# RS485_RS232_Sheet.net
KiCad netlist of a schematic drawn in Altium Designer
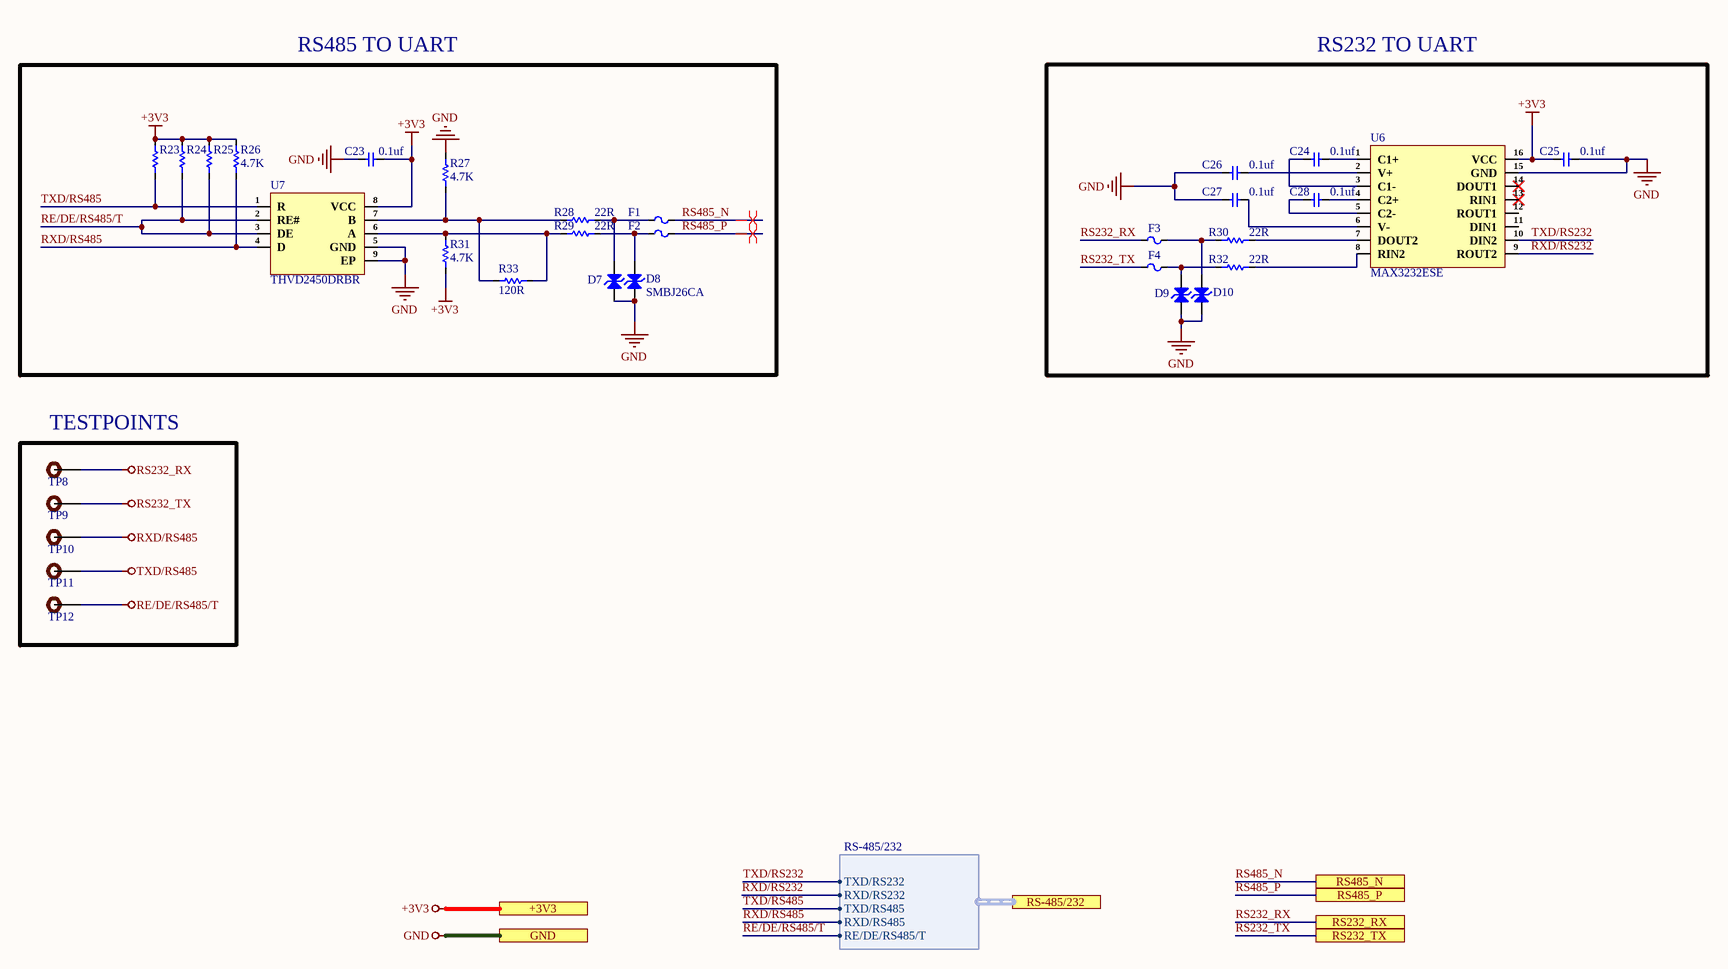
[diagram p0: RS485_RS232_Sheet.SchDoc]

(export (version "E")
  (design (tool "Eeschema 10.0.6"))
  (components
    (comp (ref "C23")
      (value "0.1uf")
      (footprint "Cap-0402")
      (description "CAP CER 0.1UF 100V X5R 0402")
      (fields
        (field (name "MANUFACTURER") "Murata")
        (field (name "MANUFACTURER PART NUMBER") "GRM155R62A104KE14D")
      )
      (libsource (lib "eSpark Libraries") (part "GRM155R62A104KE14D"))
    )
    (comp (ref "C24")
      (value "0.1uf")
      (footprint "Cap-0402")
      (description "CAP CER 0.1UF 100V X5R 0402")
      (fields
        (field (name "MANUFACTURER") "Murata")
        (field (name "MANUFACTURER PART NUMBER") "GRM155R62A104KE14D")
      )
      (libsource (lib "eSpark Libraries") (part "GRM155R62A104KE14D"))
    )
    (comp (ref "C25")
      (value "0.1uf")
      (footprint "Cap-0402")
      (description "CAP CER 0.1UF 100V X5R 0402")
      (fields
        (field (name "MANUFACTURER") "Murata")
        (field (name "MANUFACTURER PART NUMBER") "GRM155R62A104KE14D")
      )
      (libsource (lib "eSpark Libraries") (part "GRM155R62A104KE14D"))
    )
    (comp (ref "C26")
      (value "0.1uf")
      (footprint "Cap-0402")
      (description "CAP CER 0.1UF 100V X5R 0402")
      (fields
        (field (name "MANUFACTURER") "Murata")
        (field (name "MANUFACTURER PART NUMBER") "GRM155R62A104KE14D")
      )
      (libsource (lib "eSpark Libraries") (part "GRM155R62A104KE14D"))
    )
    (comp (ref "C27")
      (value "0.1uf")
      (footprint "Cap-0402")
      (description "CAP CER 0.1UF 100V X5R 0402")
      (fields
        (field (name "MANUFACTURER") "Murata")
        (field (name "MANUFACTURER PART NUMBER") "GRM155R62A104KE14D")
      )
      (libsource (lib "eSpark Libraries") (part "GRM155R62A104KE14D"))
    )
    (comp (ref "C28")
      (value "0.1uf")
      (footprint "Cap-0402")
      (description "CAP CER 0.1UF 100V X5R 0402")
      (fields
        (field (name "MANUFACTURER") "Murata")
        (field (name "MANUFACTURER PART NUMBER") "GRM155R62A104KE14D")
      )
      (libsource (lib "eSpark Libraries") (part "GRM155R62A104KE14D"))
    )
    (comp (ref "D7")
      (value "SMBJ26CA")
      (footprint "SMB Bi Directional")
      (description "SMB(DO-214AA) TVS ROHS")
      (fields (field (name "MANUFACTURER") "MSKSEMI") (field (name "LCSC PART NUMBER") "C5331111"))
      (libsource (lib "eSpark Libraries") (part "SMBJ26CA"))
    )
    (comp (ref "D8")
      (value "SMBJ26CA")
      (footprint "SMB Bi Directional")
      (description "SMB(DO-214AA) TVS ROHS")
      (fields (field (name "MANUFACTURER") "MSKSEMI") (field (name "LCSC PART NUMBER") "C5331111"))
      (libsource (lib "eSpark Libraries") (part "SMBJ26CA"))
    )
    (comp (ref "D9")
      (value "SMBJ26CA")
      (footprint "SMB Bi Directional")
      (description "SMB(DO-214AA) TVS ROHS")
      (fields (field (name "MANUFACTURER") "MSKSEMI") (field (name "LCSC PART NUMBER") "C5331111"))
      (libsource (lib "eSpark Libraries") (part "SMBJ26CA"))
    )
    (comp (ref "D10")
      (value "SMBJ26CA")
      (footprint "SMB Bi Directional")
      (description "SMB(DO-214AA) TVS ROHS")
      (fields (field (name "MANUFACTURER") "MSKSEMI") (field (name "LCSC PART NUMBER") "C5331111"))
      (libsource (lib "eSpark Libraries") (part "SMBJ26CA"))
    )
    (comp (ref "F1")
      (value "SMD0805P020TF")
      (footprint "Fuse-0805")
      (description "9V 200mA 100A 500mA 0805 Resettable Fuses ROHS")
      (fields (field (name "MANUFACTURER") "RUILON") (field (name "LCSC PART NUMBER") "C20976"))
      (libsource (lib "eSpark_centralized_Library(2022)") (part "SMD0805P020TF"))
    )
    (comp (ref "F2")
      (value "SMD0805P020TF")
      (footprint "Fuse-0805")
      (description "9V 200mA 100A 500mA 0805 Resettable Fuses ROHS")
      (fields (field (name "MANUFACTURER") "RUILON") (field (name "LCSC PART NUMBER") "C20976"))
      (libsource (lib "eSpark_centralized_Library(2022)") (part "SMD0805P020TF"))
    )
    (comp (ref "F3")
      (value "SMD0805P020TF")
      (footprint "Fuse-0805")
      (description "9V 200mA 100A 500mA 0805 Resettable Fuses ROHS")
      (fields (field (name "MANUFACTURER") "RUILON") (field (name "LCSC PART NUMBER") "C20976"))
      (libsource (lib "eSpark Libraries") (part "SMD0805P020TF"))
    )
    (comp (ref "F4")
      (value "SMD0805P020TF")
      (footprint "Fuse-0805")
      (description "9V 200mA 100A 500mA 0805 Resettable Fuses ROHS")
      (fields (field (name "MANUFACTURER") "RUILON") (field (name "LCSC PART NUMBER") "C20976"))
      (libsource (lib "eSpark Libraries") (part "SMD0805P020TF"))
    )
    (comp (ref "R23")
      (value "4.7K")
      (footprint "Res-0402")
      (description "RES 4.7K OHM 1% 1/16W 0402")
      (fields
        (field (name "MANUFACTURER") "Yageo")
        (field (name "MANUFACTURER PART NUMBER") "RC0402FR-074K7L")
      )
      (libsource (lib "eSpark Libraries") (part "RC0402FR-074K7L"))
    )
    (comp (ref "R24")
      (value "4.7K")
      (footprint "Res-0402")
      (description "RES 4.7K OHM 1% 1/16W 0402")
      (fields
        (field (name "MANUFACTURER") "Yageo")
        (field (name "MANUFACTURER PART NUMBER") "RC0402FR-074K7L")
      )
      (libsource (lib "eSpark Libraries") (part "RC0402FR-074K7L"))
    )
    (comp (ref "R25")
      (value "4.7K")
      (footprint "Res-0402")
      (description "RES 4.7K OHM 1% 1/16W 0402")
      (fields
        (field (name "MANUFACTURER") "Yageo")
        (field (name "MANUFACTURER PART NUMBER") "RC0402FR-074K7L")
      )
      (libsource (lib "eSpark Libraries") (part "RC0402FR-074K7L"))
    )
    (comp (ref "R26")
      (value "4.7K")
      (footprint "Res-0402")
      (description "RES 4.7K OHM 1% 1/16W 0402")
      (fields
        (field (name "MANUFACTURER") "Yageo")
        (field (name "MANUFACTURER PART NUMBER") "RC0402FR-074K7L")
      )
      (libsource (lib "eSpark Libraries") (part "RC0402FR-074K7L"))
    )
    (comp (ref "R27")
      (value "4.7K")
      (footprint "Res-0402")
      (description "RES 4.7K OHM 1% 1/16W 0402")
      (fields
        (field (name "MANUFACTURER") "Yageo")
        (field (name "MANUFACTURER PART NUMBER") "RC0402FR-074K7L")
      )
      (libsource (lib "eSpark Libraries") (part "RC0402FR-074K7L"))
    )
    (comp (ref "R28")
      (value "22R")
      (footprint "Res-0201")
      (description "RES 22 OHM 1% 1/20W 0201")
      (fields
        (field (name "MANUFACTURER") "Yageo")
        (field (name "MANUFACTURER PART NUMBER") "RC0201FR-0722RL")
      )
      (libsource (lib "eSpark Libraries") (part "RC0201FR-0722RL"))
    )
    (comp (ref "R29")
      (value "22R")
      (footprint "Res-0201")
      (description "RES 22 OHM 1% 1/20W 0201")
      (fields
        (field (name "MANUFACTURER") "Yageo")
        (field (name "MANUFACTURER PART NUMBER") "RC0201FR-0722RL")
      )
      (libsource (lib "eSpark Libraries") (part "RC0201FR-0722RL"))
    )
    (comp (ref "R30")
      (value "22R")
      (footprint "Res-0201")
      (description "RES 22 OHM 1% 1/20W 0201")
      (fields
        (field (name "MANUFACTURER") "Yageo")
        (field (name "MANUFACTURER PART NUMBER") "RC0201FR-0722RL")
      )
      (libsource (lib "eSpark Libraries") (part "RC0201FR-0722RL"))
    )
    (comp (ref "R31")
      (value "4.7K")
      (footprint "Res-0402")
      (description "RES 4.7K OHM 1% 1/16W 0402")
      (fields
        (field (name "MANUFACTURER") "Yageo")
        (field (name "MANUFACTURER PART NUMBER") "RC0402FR-074K7L")
      )
      (libsource (lib "eSpark Libraries") (part "RC0402FR-074K7L"))
    )
    (comp (ref "R32")
      (value "22R")
      (footprint "Res-0201")
      (description "RES 22 OHM 1% 1/20W 0201")
      (fields
        (field (name "MANUFACTURER") "Yageo")
        (field (name "MANUFACTURER PART NUMBER") "RC0201FR-0722RL")
      )
      (libsource (lib "eSpark Libraries") (part "RC0201FR-0722RL"))
    )
    (comp (ref "R33")
      (value "120R")
      (footprint "Res-0603")
      (description "RES 120 OHM 5% 1/10W 0603")
      (fields
        (field (name "MANUFACTURER") "Yageo")
        (field (name "MANUFACTURER PART NUMBER") "RC0603JR-07120RL")
      )
      (libsource (lib "eSpark Libraries") (part "RC0603JR-07120RL"))
    )
    (comp (ref "TP8")
      (value "TEST POINT")
      (footprint "Test-point")
      (description "Test Point ON")
      (libsource (lib "eSpark Libraries") (part "TEST POINT"))
    )
    (comp (ref "TP9")
      (value "TEST POINT")
      (footprint "Test-point")
      (description "Test Point ON")
      (libsource (lib "eSpark Libraries") (part "TEST POINT"))
    )
    (comp (ref "TP10")
      (value "TEST POINT")
      (footprint "Test-point")
      (description "Test Point ON")
      (libsource (lib "eSpark Libraries") (part "TEST POINT"))
    )
    (comp (ref "TP11")
      (value "TEST POINT")
      (footprint "Test-point")
      (description "Test Point ON")
      (libsource (lib "eSpark Libraries") (part "TEST POINT"))
    )
    (comp (ref "TP12")
      (value "TEST POINT")
      (footprint "Test-point")
      (description "Test Point ON")
      (libsource (lib "eSpark Libraries") (part "TEST POINT"))
    )
    (comp (ref "U6")
      (value "MAX3232ESE")
      (footprint "SOP-16")
      (description "250Kbps transceiver 2/2 SOP-16 RS232 ICs ROHS")
      (fields (field (name "MANUFACTURER") "UMW") (field (name "LCSC PART NUMBER") "C2904738"))
      (libsource (lib "eSpark Libraries") (part "MAX3232ESE"))
    )
    (comp (ref "U7")
      (value "THVD2450DRBR")
      (footprint "SON-8-EP(3x3)")
      (description "IC TRANSCEIVER HALF 1/1 8SON")
      (fields (field (name "MANUFACTURER") "Texas Instruments") (field (name "LCSC PART NUMBER") "C2878080"))
      (libsource (lib "eSpark Libraries") (part "THVD2450DRBR"))
    )
  )
  (nets
    (net (code "2") (name "+3V3") (class "Default")
      (node (ref "C23") (pin "2") (pinfunction "2_2") (pintype "passive"))
      (node (ref "C25") (pin "2") (pinfunction "2_2") (pintype "passive"))
      (node (ref "R23") (pin "2") (pinfunction "2_2") (pintype "passive"))
      (node (ref "R24") (pin "2") (pinfunction "2_2") (pintype "passive"))
      (node (ref "R25") (pin "2") (pinfunction "2_2") (pintype "passive"))
      (node (ref "R26") (pin "2") (pinfunction "2_2") (pintype "passive"))
      (node (ref "R31") (pin "1") (pinfunction "1_1") (pintype "passive"))
      (node (ref "U6") (pin "16") (pinfunction "VCC_16") (pintype "passive"))
      (node (ref "U7") (pin "8") (pinfunction "VCC_8") (pintype "passive"))
    )
    (net (code "3") (name "/RS485_N") (class "Default")
      (node (ref "F1") (pin "2") (pinfunction "2_2") (pintype "passive"))
    )
    (net (code "4") (name "/RS485_P") (class "Default")
      (node (ref "F2") (pin "2") (pinfunction "2_2") (pintype "passive"))
    )
    (net (code "5") (name "/RXD{slash}RS232") (class "Default")
      (node (ref "U6") (pin "9") (pinfunction "ROUT2_9") (pintype "passive"))
    )
    (net (code "6") (name "/TXD{slash}RS232") (class "Default")
      (node (ref "U6") (pin "10") (pinfunction "DIN2_10") (pintype "passive"))
    )
    (net (code "8") (name "GND") (class "Default")
      (node (ref "C23") (pin "1") (pinfunction "1_1") (pintype "passive"))
      (node (ref "C25") (pin "1") (pinfunction "1_1") (pintype "passive"))
      (node (ref "C26") (pin "1") (pinfunction "1_1") (pintype "passive"))
      (node (ref "C27") (pin "1") (pinfunction "1_1") (pintype "passive"))
      (node (ref "D10") (pin "1") (pinfunction "A_1") (pintype "passive"))
      (node (ref "D7") (pin "1") (pinfunction "A_1") (pintype "passive"))
      (node (ref "D8") (pin "1") (pinfunction "A_1") (pintype "passive"))
      (node (ref "D9") (pin "1") (pinfunction "A_1") (pintype "passive"))
      (node (ref "R27") (pin "2") (pinfunction "2_2") (pintype "passive"))
      (node (ref "U6") (pin "15") (pinfunction "GND_15") (pintype "passive"))
      (node (ref "U7") (pin "5") (pinfunction "GND_5") (pintype "passive"))
      (node (ref "U7") (pin "9") (pinfunction "EP_9") (pintype "passive"))
    )
    (net (code "9") (name "Net-(D7-K)") (class "Default")
      (node (ref "D7") (pin "2") (pinfunction "K_2") (pintype "passive"))
      (node (ref "F1") (pin "1") (pinfunction "1_1") (pintype "passive"))
      (node (ref "R28") (pin "2") (pinfunction "2_2") (pintype "passive"))
    )
    (net (code "10") (name "Net-(D8-K)") (class "Default")
      (node (ref "D8") (pin "2") (pinfunction "K_2") (pintype "passive"))
      (node (ref "F2") (pin "1") (pinfunction "1_1") (pintype "passive"))
      (node (ref "R29") (pin "2") (pinfunction "2_2") (pintype "passive"))
    )
    (net (code "11") (name "Net-(D9-K)") (class "Default")
      (node (ref "D9") (pin "2") (pinfunction "K_2") (pintype "passive"))
      (node (ref "F4") (pin "2") (pinfunction "2_2") (pintype "passive"))
      (node (ref "R32") (pin "1") (pinfunction "1_1") (pintype "passive"))
    )
    (net (code "12") (name "Net-(D10-K)") (class "Default")
      (node (ref "D10") (pin "2") (pinfunction "K_2") (pintype "passive"))
      (node (ref "F3") (pin "2") (pinfunction "2_2") (pintype "passive"))
      (node (ref "R30") (pin "1") (pinfunction "1_1") (pintype "passive"))
    )
    (net (code "13") (name "Net-(U6-C1+)") (class "Default")
      (node (ref "C24") (pin "1") (pinfunction "1_1") (pintype "passive"))
      (node (ref "U6") (pin "1") (pinfunction "C1+_1") (pintype "passive"))
    )
    (net (code "14") (name "Net-(U6-C1-)") (class "Default")
      (node (ref "C24") (pin "2") (pinfunction "2_2") (pintype "passive"))
      (node (ref "U6") (pin "3") (pinfunction "C1-_3") (pintype "passive"))
    )
    (net (code "15") (name "Net-(U6-C2+)") (class "Default")
      (node (ref "C28") (pin "1") (pinfunction "1_1") (pintype "passive"))
      (node (ref "U6") (pin "4") (pinfunction "C2+_4") (pintype "passive"))
    )
    (net (code "16") (name "Net-(U6-C2-)") (class "Default")
      (node (ref "C28") (pin "2") (pinfunction "2_2") (pintype "passive"))
      (node (ref "U6") (pin "5") (pinfunction "C2-_5") (pintype "passive"))
    )
    (net (code "17") (name "Net-(U6-DOUT2)") (class "Default")
      (node (ref "R30") (pin "2") (pinfunction "2_2") (pintype "passive"))
      (node (ref "U6") (pin "7") (pinfunction "DOUT2_7") (pintype "passive"))
    )
    (net (code "18") (name "Net-(U6-RIN2)") (class "Default")
      (node (ref "R32") (pin "2") (pinfunction "2_2") (pintype "passive"))
      (node (ref "U6") (pin "8") (pinfunction "RIN2_8") (pintype "passive"))
    )
    (net (code "19") (name "Net-(U6-V+)") (class "Default")
      (node (ref "C26") (pin "2") (pinfunction "2_2") (pintype "passive"))
      (node (ref "U6") (pin "2") (pinfunction "V+_2") (pintype "passive"))
    )
    (net (code "20") (name "Net-(U6-V-)") (class "Default")
      (node (ref "C27") (pin "2") (pinfunction "2_2") (pintype "passive"))
      (node (ref "U6") (pin "6") (pinfunction "V-_6") (pintype "passive"))
    )
    (net (code "21") (name "Net-(U7-A)") (class "Default")
      (node (ref "R29") (pin "1") (pinfunction "1_1") (pintype "passive"))
      (node (ref "R31") (pin "2") (pinfunction "2_2") (pintype "passive"))
      (node (ref "R33") (pin "2") (pinfunction "2_2") (pintype "passive"))
      (node (ref "U7") (pin "6") (pinfunction "A_6") (pintype "passive"))
    )
    (net (code "22") (name "Net-(U7-B)") (class "Default")
      (node (ref "R27") (pin "1") (pinfunction "1_1") (pintype "passive"))
      (node (ref "R28") (pin "1") (pinfunction "1_1") (pintype "passive"))
      (node (ref "R33") (pin "1") (pinfunction "1_1") (pintype "passive"))
      (node (ref "U7") (pin "7") (pinfunction "B_7") (pintype "passive"))
    )
    (net (code "23") (name "RE{slash}DE{slash}RS485{slash}T") (class "Default")
      (node (ref "R24") (pin "1") (pinfunction "1_1") (pintype "passive"))
      (node (ref "R25") (pin "1") (pinfunction "1_1") (pintype "passive"))
      (node (ref "TP12") (pin "1") (pinfunction "1_1") (pintype "passive"))
      (node (ref "U7") (pin "2") (pinfunction "RE#_2") (pintype "passive"))
      (node (ref "U7") (pin "3") (pinfunction "DE_3") (pintype "passive"))
    )
    (net (code "24") (name "RS232_RX") (class "Default")
      (node (ref "F3") (pin "1") (pinfunction "1_1") (pintype "passive"))
      (node (ref "TP8") (pin "1") (pinfunction "1_1") (pintype "passive"))
    )
    (net (code "25") (name "RS232_TX") (class "Default")
      (node (ref "F4") (pin "1") (pinfunction "1_1") (pintype "passive"))
      (node (ref "TP9") (pin "1") (pinfunction "1_1") (pintype "passive"))
    )
    (net (code "26") (name "RXD{slash}RS485") (class "Default")
      (node (ref "R26") (pin "1") (pinfunction "1_1") (pintype "passive"))
      (node (ref "TP10") (pin "1") (pinfunction "1_1") (pintype "passive"))
      (node (ref "U7") (pin "4") (pinfunction "D_4") (pintype "passive"))
    )
    (net (code "27") (name "TXD{slash}RS485") (class "Default")
      (node (ref "R23") (pin "1") (pinfunction "1_1") (pintype "passive"))
      (node (ref "TP11") (pin "1") (pinfunction "1_1") (pintype "passive"))
      (node (ref "U7") (pin "1") (pinfunction "R_1") (pintype "passive"))
    )
    (net (code "28") (name "unconnected-(U6-DIN1-Pad11)") (class "Default")
      (node (ref "U6") (pin "11") (pinfunction "DIN1_11") (pintype "passive"))
    )
    (net (code "29") (name "unconnected-(U6-DOUT1-Pad14)") (class "Default")
      (node (ref "U6") (pin "14") (pinfunction "DOUT1_14") (pintype "passive+no_connect"))
    )
    (net (code "30") (name "unconnected-(U6-RIN1-Pad13)") (class "Default")
      (node (ref "U6") (pin "13") (pinfunction "RIN1_13") (pintype "passive+no_connect"))
    )
    (net (code "31") (name "unconnected-(U6-ROUT1-Pad12)") (class "Default")
      (node (ref "U6") (pin "12") (pinfunction "ROUT1_12") (pintype "passive"))
    )
  )
)
